# ControleurInterface.net
KiCad netlist of a schematic drawn in Altium Designer
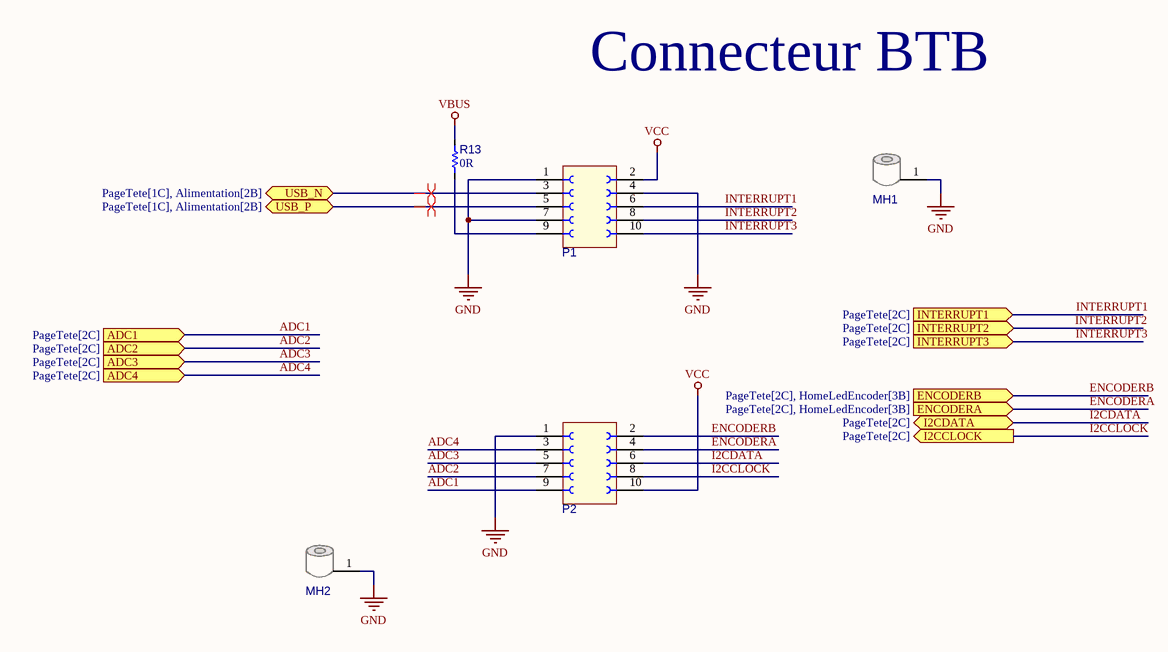
[diagram p0: ControleurInterface.SchDoc]

(export (version "E")
  (design (tool "Eeschema 10.0.6"))
  (components
    (comp (ref "MH1")
      (value "SMTSO1430MTJ")
      (footprint "MP_Standoff_M1.4x3mm_SMT")
      (description "Mounting Standoff Threaded 1.4mm, stack height 3mm, SMD")
      (libsource (lib "243-336_MP_Manette_ETU") (part "MP_1.4MM_3MM_SMD"))
    )
    (comp (ref "MH2")
      (value "SMTSO1430MTJ")
      (footprint "MP_Standoff_M1.4x3mm_SMT")
      (description "Mounting Standoff Threaded 1.4mm, stack height 3mm, SMD")
      (libsource (lib "243-336_MP_Manette_ETU") (part "MP_1.4MM_3MM_SMD"))
    )
    (comp (ref "P1")
      (value "HC-PBB12NB(3.0)-10DP-0.5V-03")
      (footprint "P_CONN_HDR_2ROW_10POS_0MM5")
      (description "Connector Header 2x5pos, 0,5mm")
      (libsource (lib "243-336_MP_Manette_ETU") (part "Conn_02x05_Header"))
    )
    (comp (ref "P2")
      (value "HC-PBB12NB(3.0)-10DP-0.5V-03")
      (footprint "P_CONN_HDR_2ROW_10POS_0MM5")
      (description "Connector Header 2x5pos, 0,5mm")
      (libsource (lib "243-336_MP_Manette_ETU") (part "Conn_02x05_Header"))
    )
    (comp (ref "R13")
      (value "0R")
      (footprint "R_1005[0402]")
      (description "Resistor type 1")
      (fields (field (name "Comment") "Res 0R 0402"))
      (libsource (lib "TEP_243-Altium_RLC-Lib") (part "RES005"))
    )
  )
  (nets
    (net (code "1") (name "/ADC1") (class "Default")
      (node (ref "P2") (pin "9") (pinfunction "9_9") (pintype "passive"))
    )
    (net (code "2") (name "/ADC2") (class "Default")
      (node (ref "P2") (pin "7") (pinfunction "7_7") (pintype "passive"))
    )
    (net (code "3") (name "/ADC3") (class "Default")
      (node (ref "P2") (pin "5") (pinfunction "5_5") (pintype "passive"))
    )
    (net (code "4") (name "/ADC4") (class "Default")
      (node (ref "P2") (pin "3") (pinfunction "3_3") (pintype "passive"))
    )
    (net (code "5") (name "/ENCODERA") (class "Default")
      (node (ref "P2") (pin "4") (pinfunction "4_4") (pintype "passive"))
    )
    (net (code "6") (name "/ENCODERB") (class "Default")
      (node (ref "P2") (pin "2") (pinfunction "2_2") (pintype "passive"))
    )
    (net (code "7") (name "/I2CCLOCK") (class "Default")
      (node (ref "P2") (pin "8") (pinfunction "8_8") (pintype "passive"))
    )
    (net (code "8") (name "/I2CDATA") (class "Default")
      (node (ref "P2") (pin "6") (pinfunction "6_6") (pintype "passive"))
    )
    (net (code "9") (name "/INTERRUPT1") (class "Default")
      (node (ref "P1") (pin "6") (pinfunction "6_6") (pintype "passive"))
    )
    (net (code "10") (name "/INTERRUPT2") (class "Default")
      (node (ref "P1") (pin "8") (pinfunction "8_8") (pintype "passive"))
    )
    (net (code "11") (name "/INTERRUPT3") (class "Default")
      (node (ref "P1") (pin "10") (pinfunction "10_10") (pintype "passive"))
    )
    (net (code "12") (name "/USB_N") (class "Default")
      (node (ref "P1") (pin "3") (pinfunction "3_3") (pintype "passive"))
    )
    (net (code "13") (name "/USB_P") (class "Default")
      (node (ref "P1") (pin "5") (pinfunction "5_5") (pintype "passive"))
    )
    (net (code "14") (name "GND") (class "Default")
      (node (ref "MH1") (pin "1") (pinfunction "1_1") (pintype "power_in"))
      (node (ref "MH2") (pin "1") (pinfunction "1_1") (pintype "power_in"))
      (node (ref "P1") (pin "1") (pinfunction "1_1") (pintype "passive"))
      (node (ref "P1") (pin "4") (pinfunction "4_4") (pintype "passive"))
      (node (ref "P1") (pin "7") (pinfunction "7_7") (pintype "passive"))
      (node (ref "P2") (pin "1") (pinfunction "1_1") (pintype "passive"))
    )
    (net (code "15") (name "Net-(P1-Pad9)") (class "Default")
      (node (ref "P1") (pin "9") (pinfunction "9_9") (pintype "passive"))
      (node (ref "R13") (pin "1") (pinfunction "1_1") (pintype "passive"))
    )
    (net (code "16") (name "VBUS") (class "Default")
      (node (ref "R13") (pin "2") (pinfunction "2_2") (pintype "passive"))
    )
    (net (code "17") (name "VCC") (class "Default")
      (node (ref "P1") (pin "2") (pinfunction "2_2") (pintype "passive"))
      (node (ref "P2") (pin "10") (pinfunction "10_10") (pintype "passive"))
    )
  )
)
